# SheetCopied.net
KiCad netlist of a schematic drawn in Altium Designer
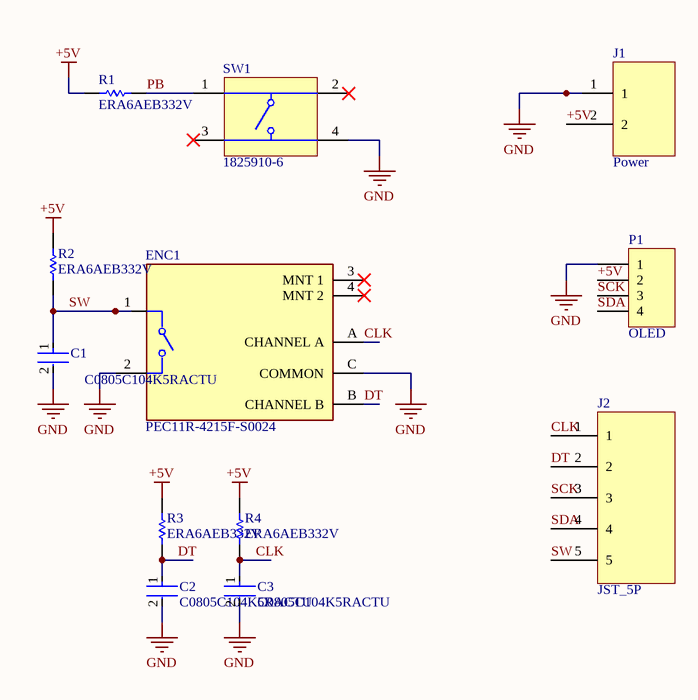
[diagram p0: SheetCopied.SchDoc]

(export (version "E")
  (design (tool "Eeschema 10.0.6"))
  (components
    (comp (ref "C1")
      (value "C0805C104K5RACTU")
      (footprint "FP-C0805C-DN-MFG")
      (description "CAP CER 0.1UF 50V X7R 0805")
      (fields
        (field (name "MANUFACTURER") "KEMET")
        (field (name "OCTOPART") "https://octopart.com/c0805c104k5ractu-kemet-143926")
      )
      (libsource (lib "Altium Content Vault") (part "b4654b650e69147ec39a6b967a45e02"))
    )
    (comp (ref "C2")
      (value "C0805C104K5RACTU")
      (footprint "FP-C0805C-DN-MFG")
      (description "CAP CER 0.1UF 50V X7R 0805")
      (fields
        (field (name "MANUFACTURER") "KEMET")
        (field (name "OCTOPART") "https://octopart.com/c0805c104k5ractu-kemet-143926")
      )
      (libsource (lib "Altium Content Vault") (part "b4654b650e69147ec39a6b967a45e02"))
    )
    (comp (ref "C3")
      (value "C0805C104K5RACTU")
      (footprint "FP-C0805C-DN-MFG")
      (description "CAP CER 0.1UF 50V X7R 0805")
      (fields
        (field (name "MANUFACTURER") "KEMET")
        (field (name "OCTOPART") "https://octopart.com/c0805c104k5ractu-kemet-143926")
      )
      (libsource (lib "Altium Content Vault") (part "b4654b650e69147ec39a6b967a45e02"))
    )
    (comp (ref "ENC1")
      (value "PEC11R-4215F-S0024")
      (footprint "FP-PEC11R-4215F-S0024-MFG")
      (description "ROTARY ENCODER MECHANICAL 24PPR")
      (libsource (lib "Altium Content Vault") (part "5f1dd25a4c49fa66e7eeb899730fe11"))
    )
    (comp (ref "J1") (value "Power") (footprint "JST_2P") (libsource (lib "Schlib") (part "JST_2P")))
    (comp (ref "J2") (value "JST_5P") (footprint "JST_5P") (libsource (lib "Schlib") (part "JST_5P")))
    (comp (ref "P1")
      (value "OLED")
      (footprint "HDR1X4")
      (description "Header, 4-Pin")
      (fields (field (name "PUBLISHER") "Altium Limited"))
      (libsource (lib "Miscellaneous Connectors") (part "Header 4"))
    )
    (comp (ref "R1")
      (value "ERA6AEB332V")
      (footprint "RESC2013X60X40ML20T25")
      (fields (field (name "MANUFACTURER") "Panasonic"))
      (libsource (lib "Altium Content Vault") (part "RES"))
    )
    (comp (ref "R2")
      (value "ERA6AEB332V")
      (footprint "RESC2013X60X40ML20T25")
      (fields (field (name "MANUFACTURER") "Panasonic"))
      (libsource (lib "Altium Content Vault") (part "RES"))
    )
    (comp (ref "R3")
      (value "ERA6AEB332V")
      (footprint "RESC2013X60X40ML20T25")
      (fields (field (name "MANUFACTURER") "Panasonic"))
      (libsource (lib "Altium Content Vault") (part "RES"))
    )
    (comp (ref "R4")
      (value "ERA6AEB332V")
      (footprint "RESC2013X60X40ML20T25")
      (fields (field (name "MANUFACTURER") "Panasonic"))
      (libsource (lib "Altium Content Vault") (part "RES"))
    )
    (comp (ref "SW1")
      (value "1825910-6")
      (footprint "TECO-1825910-6_V")
      (description "Tact Switch, SPST-NO, 0.05 A, -35 to 85 degC, 4-Pin THD, RoHS, Bulk")
      (fields (field (name "MANUFACTURER") "TE Connectivity"))
      (libsource (lib "Altium Content Vault") (part "SW-SPST-4_A"))
    )
  )
  (nets
    (net (code "1") (name "+5V") (class "Default")
      (node (ref "J1") (pin "2") (pinfunction "2_2") (pintype "passive"))
      (node (ref "P1") (pin "2") (pinfunction "2_2") (pintype "passive"))
      (node (ref "R1") (pin "1") (pinfunction "1_1") (pintype "passive"))
      (node (ref "R2") (pin "2") (pinfunction "2_2") (pintype "passive"))
      (node (ref "R3") (pin "2") (pinfunction "2_2") (pintype "passive"))
      (node (ref "R4") (pin "2") (pinfunction "2_2") (pintype "passive"))
    )
    (net (code "2") (name "/CLK") (class "Default")
      (node (ref "C3") (pin "1") (pinfunction "1_1") (pintype "passive"))
      (node (ref "ENC1") (pin "A") (pinfunction "CHANNEL_A_A") (pintype "passive"))
      (node (ref "J2") (pin "1") (pinfunction "1_1") (pintype "power_in"))
      (node (ref "R4") (pin "1") (pinfunction "1_1") (pintype "passive"))
    )
    (net (code "3") (name "/DT") (class "Default")
      (node (ref "C2") (pin "1") (pinfunction "1_1") (pintype "passive"))
      (node (ref "ENC1") (pin "B") (pinfunction "CHANNEL_B_B") (pintype "passive"))
      (node (ref "J2") (pin "2") (pinfunction "2_2") (pintype "power_in"))
      (node (ref "R3") (pin "1") (pinfunction "1_1") (pintype "passive"))
    )
    (net (code "4") (name "/PB") (class "Default")
      (node (ref "R1") (pin "2") (pinfunction "2_2") (pintype "passive"))
      (node (ref "SW1") (pin "1") (pinfunction "1_1") (pintype "passive"))
    )
    (net (code "5") (name "/SCK") (class "Default")
      (node (ref "J2") (pin "3") (pinfunction "3_3") (pintype "passive"))
      (node (ref "P1") (pin "3") (pinfunction "3_3") (pintype "passive"))
    )
    (net (code "6") (name "/SDA") (class "Default")
      (node (ref "J2") (pin "4") (pinfunction "4_4") (pintype "passive"))
      (node (ref "P1") (pin "4") (pinfunction "4_4") (pintype "passive"))
    )
    (net (code "7") (name "/SW") (class "Default")
      (node (ref "C1") (pin "1") (pinfunction "1_1") (pintype "passive"))
      (node (ref "ENC1") (pin "1") (pinfunction "1_1") (pintype "passive"))
      (node (ref "J2") (pin "5") (pinfunction "5_5") (pintype "passive"))
      (node (ref "R2") (pin "1") (pinfunction "1_1") (pintype "passive"))
    )
    (net (code "8") (name "GND") (class "Default")
      (node (ref "C1") (pin "2") (pinfunction "2_2") (pintype "passive"))
      (node (ref "C2") (pin "2") (pinfunction "2_2") (pintype "passive"))
      (node (ref "C3") (pin "2") (pinfunction "2_2") (pintype "passive"))
      (node (ref "ENC1") (pin "2") (pinfunction "2_2") (pintype "passive"))
      (node (ref "ENC1") (pin "C") (pinfunction "COMMON_C") (pintype "passive"))
      (node (ref "J1") (pin "1") (pinfunction "1_1") (pintype "passive"))
      (node (ref "P1") (pin "1") (pinfunction "1_1") (pintype "passive"))
      (node (ref "SW1") (pin "4") (pinfunction "4_4") (pintype "passive"))
    )
    (net (code "9") (name "unconnected-(ENC1-MNT_1-Pad3)") (class "Default")
      (node (ref "ENC1") (pin "3") (pinfunction "MNT_1_3") (pintype "passive+no_connect"))
    )
    (net (code "10") (name "unconnected-(ENC1-MNT_2-Pad4)") (class "Default")
      (node (ref "ENC1") (pin "4") (pinfunction "MNT_2_4") (pintype "passive+no_connect"))
    )
    (net (code "11") (name "unconnected-(SW1-Pad2)") (class "Default")
      (node (ref "SW1") (pin "2") (pinfunction "2_2") (pintype "passive+no_connect"))
    )
    (net (code "12") (name "unconnected-(SW1-Pad3)") (class "Default")
      (node (ref "SW1") (pin "3") (pinfunction "3_3") (pintype "passive+no_connect"))
    )
  )
)
